# Y-babies_ATtiny84_v04.net
KiCad netlist of a schematic drawn in EAGLE
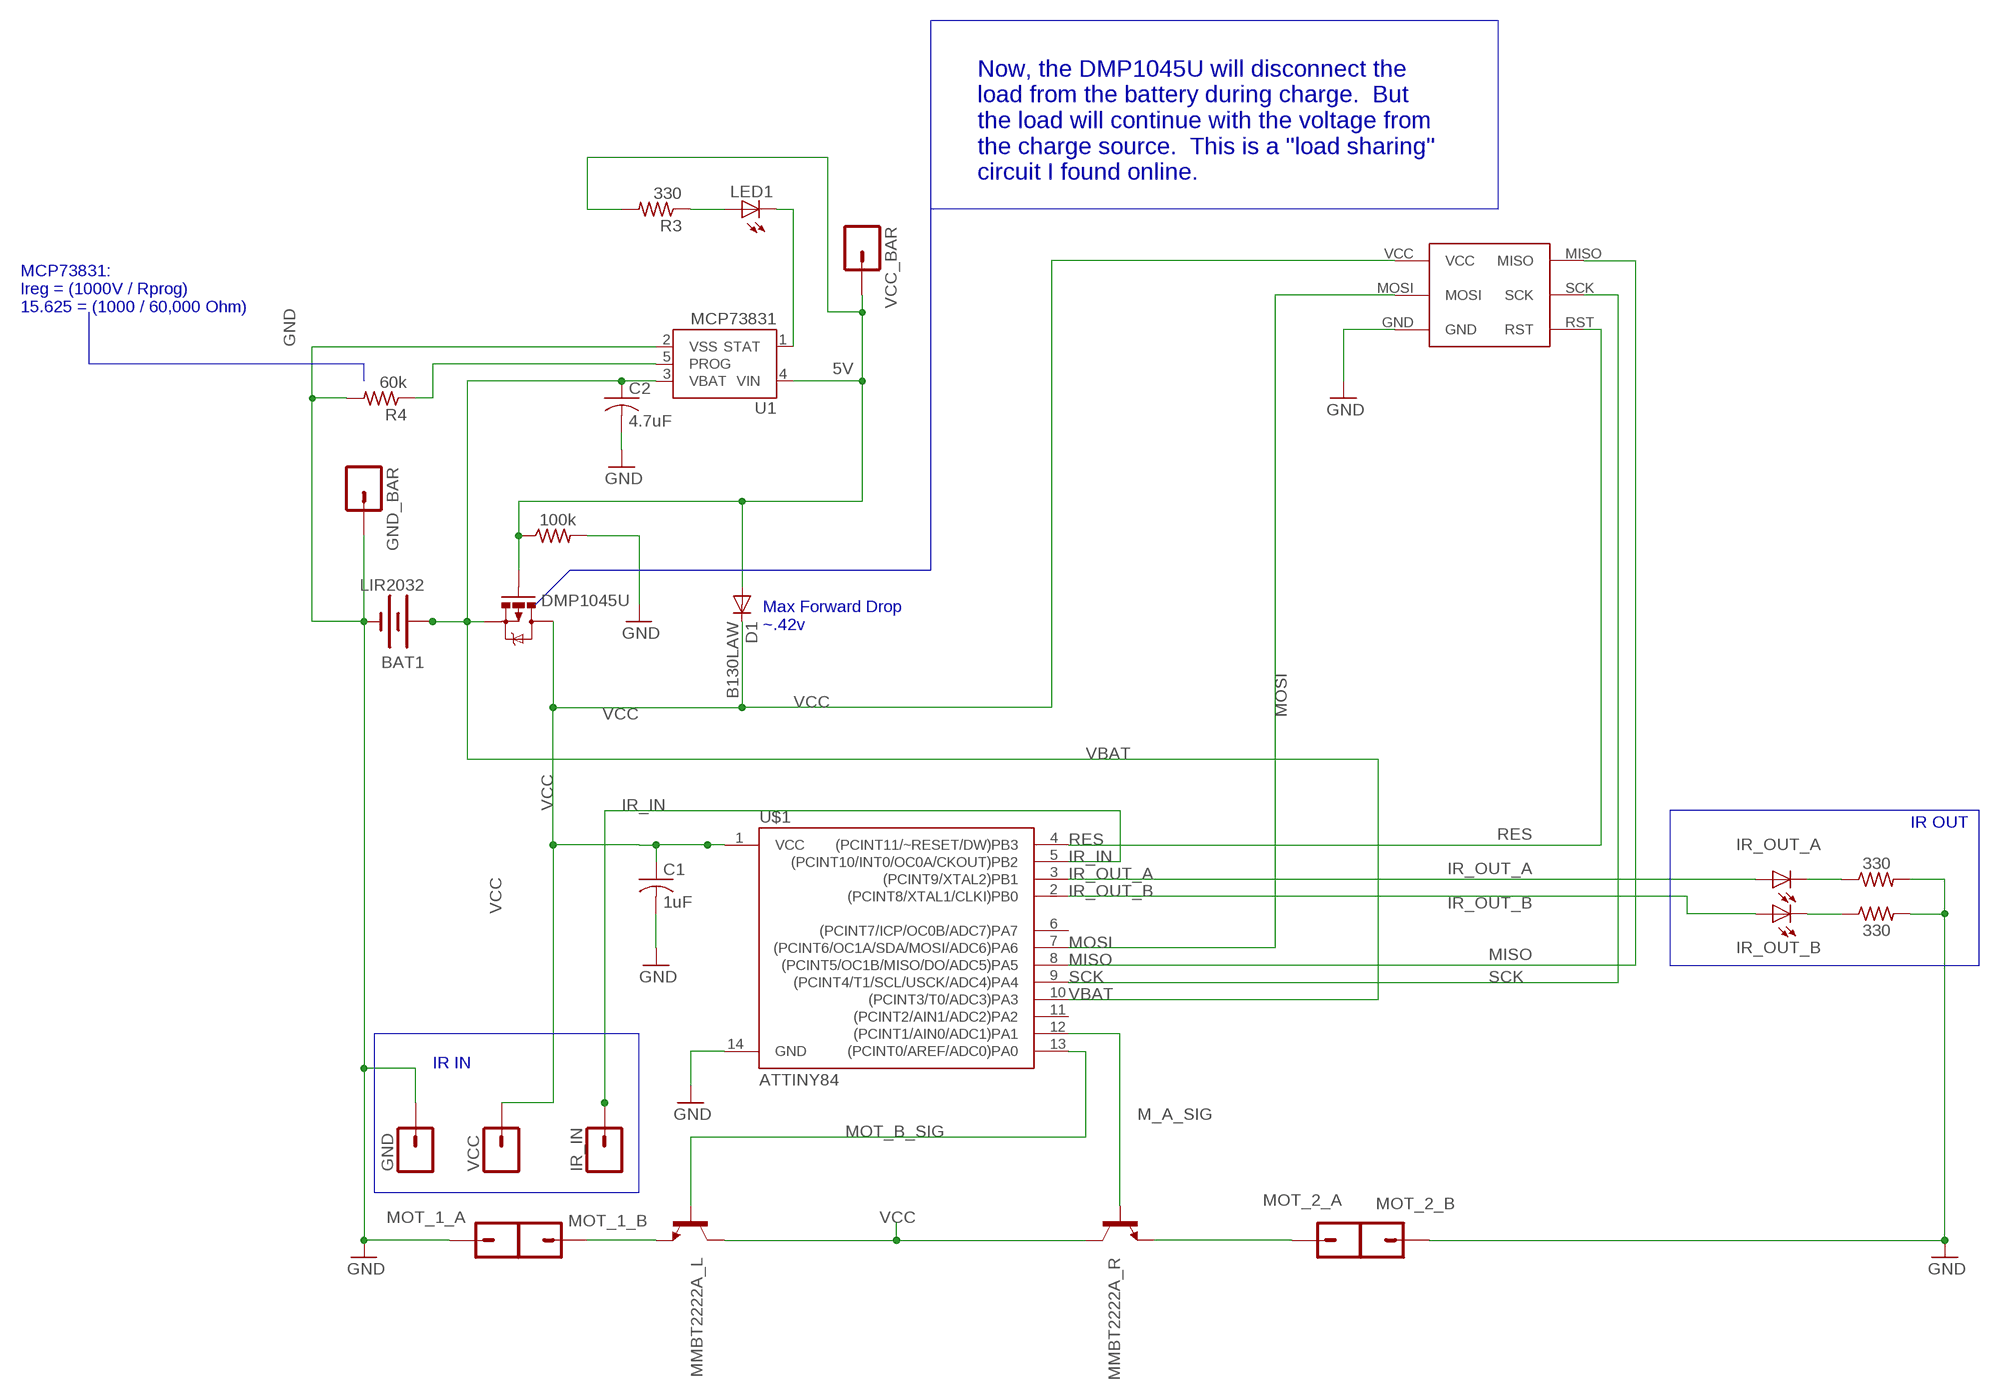
[diagram p0: schematic, sheet 1]

(export (version "E")
  (design (tool "Eeschema 10.0.6"))
  (components
    (comp (ref "BAT1")
      (value "LIR2032")
      (footprint "eagle-import:BATTCOM_20MM_PTH")
      (libsource (lib "eagle-import") (part "BATTERY20PTH"))
    )
    (comp (ref "C1")
      (value "1uF")
      (footprint "eagle-import:C0402K")
      (libsource (lib "eagle-import") (part "C-USC0402K"))
    )
    (comp (ref "C2")
      (value "4.7uF")
      (footprint "eagle-import:C0805K")
      (libsource (lib "eagle-import") (part "C-USC0805K"))
    )
    (comp (ref "D1")
      (value "B130LAW")
      (footprint "eagle-import:SOD123")
      (libsource (lib "eagle-import") (part "DIODE-SOD123"))
    )
    (comp (ref "DMP1045U")
      (value "MOSFET-PCHANNELSMD")
      (footprint "eagle-import:SOT23-3")
      (libsource (lib "eagle-import") (part "MOSFET-PCHANNELSMD"))
    )
    (comp (ref "GND")
      (value "M01PTH")
      (footprint "eagle-import:1X01")
      (libsource (lib "eagle-import") (part "M01PTH"))
    )
    (comp (ref "GND_BAR")
      (value "M01PTH")
      (footprint "eagle-import:1X01")
      (libsource (lib "eagle-import") (part "M01PTH"))
    )
    (comp (ref "IR_IN")
      (value "M01PTH")
      (footprint "eagle-import:1X01")
      (libsource (lib "eagle-import") (part "M01PTH"))
    )
    (comp (ref "IR_OUT_A")
      (value "LED3MM")
      (footprint "eagle-import:LED3MM")
      (libsource (lib "eagle-import") (part "LED3MM"))
    )
    (comp (ref "IR_OUT_B")
      (value "LED3MM")
      (footprint "eagle-import:LED3MM")
      (libsource (lib "eagle-import") (part "LED3MM"))
    )
    (comp (ref "LED1")
      (value "LEDSML0603")
      (footprint "eagle-import:SML0603")
      (libsource (lib "eagle-import") (part "LEDSML0603"))
    )
    (comp (ref "MMBT2222A_L")
      (value "TRANSISTOR_NPNSOT23")
      (footprint "eagle-import:SOT23")
      (libsource (lib "eagle-import") (part "TRANSISTOR_NPNSOT23"))
    )
    (comp (ref "MMBT2222A_R")
      (value "TRANSISTOR_NPNSOT23")
      (footprint "eagle-import:SOT23")
      (libsource (lib "eagle-import") (part "TRANSISTOR_NPNSOT23"))
    )
    (comp (ref "MOT_1_A")
      (value "M01SMD-4.5X1.5")
      (footprint "eagle-import:PAD-1.5X4.5")
      (libsource (lib "eagle-import") (part "M01SMD-4.5X1.5"))
    )
    (comp (ref "MOT_1_B")
      (value "M01SMD-4.5X1.5")
      (footprint "eagle-import:PAD-1.5X4.5")
      (libsource (lib "eagle-import") (part "M01SMD-4.5X1.5"))
    )
    (comp (ref "MOT_2_A")
      (value "M01SMD-4.5X1.5")
      (footprint "eagle-import:PAD-1.5X4.5")
      (libsource (lib "eagle-import") (part "M01SMD-4.5X1.5"))
    )
    (comp (ref "MOT_2_B")
      (value "M01SMD-4.5X1.5")
      (footprint "eagle-import:PAD-1.5X4.5")
      (libsource (lib "eagle-import") (part "M01SMD-4.5X1.5"))
    )
    (comp (ref "R1")
      (value "330")
      (footprint "eagle-import:R0402")
      (libsource (lib "eagle-import") (part "R-US_R0402"))
    )
    (comp (ref "R2")
      (value "330")
      (footprint "eagle-import:R0402")
      (libsource (lib "eagle-import") (part "R-US_R0402"))
    )
    (comp (ref "R3")
      (value "330")
      (footprint "eagle-import:R0402")
      (libsource (lib "eagle-import") (part "R-US_R0402"))
    )
    (comp (ref "R4")
      (value "60k")
      (footprint "eagle-import:R0402")
      (libsource (lib "eagle-import") (part "R-US_R0402"))
    )
    (comp (ref "R5")
      (value "100k")
      (footprint "eagle-import:R0402")
      (libsource (lib "eagle-import") (part "R-US_R0402"))
    )
    (comp (ref "U$1")
      (value "ATTINY84")
      (footprint "eagle-import:SO14")
      (libsource (lib "eagle-import") (part "ATTINY84"))
    )
    (comp (ref "U$2")
      (value "POGO_PIN_SPI_PAD")
      (footprint "eagle-import:POGO_PIN_SPI_PAD")
      (libsource (lib "eagle-import") (part "POGO_PIN_SPI_PAD"))
    )
    (comp (ref "U1")
      (value "MCP73831")
      (footprint "eagle-import:SOT23-5")
      (libsource (lib "eagle-import") (part "MCP73831"))
    )
    (comp (ref "VCC")
      (value "M01PTH")
      (footprint "eagle-import:1X01")
      (libsource (lib "eagle-import") (part "M01PTH"))
    )
    (comp (ref "VCC_BAR")
      (value "M01PTH")
      (footprint "eagle-import:1X01")
      (libsource (lib "eagle-import") (part "M01PTH"))
    )
  )
  (nets
    (net (code "1") (name "/5V") (class "Default")
      (node (ref "D1") (pin "A") (pinfunction "A_A") (pintype "passive"))
      (node (ref "DMP1045U") (pin "1") (pinfunction "G_1") (pintype "passive"))
      (node (ref "R3") (pin "2") (pinfunction "2_2") (pintype "passive"))
      (node (ref "R5") (pin "1") (pinfunction "1_1") (pintype "passive"))
      (node (ref "U1") (pin "4") (pinfunction "VIN_4") (pintype "power_in"))
      (node (ref "VCC_BAR") (pin "1") (pinfunction "1_1") (pintype "passive"))
    )
    (net (code "2") (name "/IR_IN") (class "Default")
      (node (ref "IR_IN") (pin "1") (pinfunction "1_1") (pintype "passive"))
      (node (ref "U$1") (pin "5") (pinfunction "(PCINT10/INT0/OC0A/CKOUT)PB2_5") (pintype "bidirectional"))
    )
    (net (code "3") (name "/IR_OUT_A") (class "Default")
      (node (ref "IR_OUT_A") (pin "A") (pinfunction "A_A") (pintype "passive"))
      (node (ref "U$1") (pin "3") (pinfunction "(PCINT9/XTAL2)PB1_3") (pintype "bidirectional"))
    )
    (net (code "4") (name "/IR_OUT_B") (class "Default")
      (node (ref "IR_OUT_B") (pin "A") (pinfunction "A_A") (pintype "passive"))
      (node (ref "U$1") (pin "2") (pinfunction "(PCINT8/XTAL1/CLKI)PB0_2") (pintype "bidirectional"))
    )
    (net (code "5") (name "/MISO") (class "Default")
      (node (ref "U$1") (pin "8") (pinfunction "(PCINT5/OC1B/MISO/DO/ADC5)PA5_8") (pintype "bidirectional"))
      (node (ref "U$2") (pin "MISO") (pinfunction "MISO_MISO") (pintype "bidirectional"))
    )
    (net (code "6") (name "/MOSI") (class "Default")
      (node (ref "U$1") (pin "7") (pinfunction "(PCINT6/OC1A/SDA/MOSI/ADC6)PA6_7") (pintype "bidirectional"))
      (node (ref "U$2") (pin "MOSI") (pinfunction "MOSI_MOSI") (pintype "bidirectional"))
    )
    (net (code "7") (name "/MOT_B_SIG") (class "Default")
      (node (ref "MMBT2222A_L") (pin "1") (pinfunction "B_1") (pintype "passive"))
      (node (ref "U$1") (pin "13") (pinfunction "(PCINT0/AREF/ADC0)PA0_13") (pintype "bidirectional"))
    )
    (net (code "8") (name "/M_A_SIG") (class "Default")
      (node (ref "MMBT2222A_R") (pin "1") (pinfunction "B_1") (pintype "passive"))
      (node (ref "U$1") (pin "12") (pinfunction "(PCINT1/AIN0/ADC1)PA1_12") (pintype "bidirectional"))
    )
    (net (code "9") (name "/RES") (class "Default")
      (node (ref "U$1") (pin "4") (pinfunction "(PCINT11/~{RESET/DW})PB3_4") (pintype "bidirectional"))
      (node (ref "U$2") (pin "RST") (pinfunction "RST_RST") (pintype "bidirectional"))
    )
    (net (code "10") (name "/SCK") (class "Default")
      (node (ref "U$1") (pin "9") (pinfunction "(PCINT4/T1/SCL/USCK/ADC4)PA4_9") (pintype "bidirectional"))
      (node (ref "U$2") (pin "SCK") (pinfunction "SCK_SCK") (pintype "bidirectional"))
    )
    (net (code "11") (name "/VBAT") (class "Default")
      (node (ref "BAT1") (pin "1") (pinfunction "+_1") (pintype "power_in"))
      (node (ref "C2") (pin "1") (pinfunction "1_1") (pintype "passive"))
      (node (ref "DMP1045U") (pin "2") (pinfunction "S_2") (pintype "passive"))
      (node (ref "U$1") (pin "10") (pinfunction "(PCINT3/T0/ADC3)PA3_10") (pintype "bidirectional"))
      (node (ref "U1") (pin "3") (pinfunction "VBAT_3") (pintype "power_in"))
    )
    (net (code "12") (name "/VCC") (class "Default")
      (node (ref "C1") (pin "1") (pinfunction "1_1") (pintype "passive"))
      (node (ref "D1") (pin "C") (pinfunction "C_C") (pintype "passive"))
      (node (ref "DMP1045U") (pin "3") (pinfunction "D_3") (pintype "passive"))
      (node (ref "MMBT2222A_L") (pin "3") (pinfunction "C_3") (pintype "passive"))
      (node (ref "MMBT2222A_R") (pin "3") (pinfunction "C_3") (pintype "passive"))
      (node (ref "U$1") (pin "1") (pinfunction "VCC_1") (pintype "bidirectional"))
      (node (ref "U$2") (pin "VCC") (pinfunction "VCC_VCC") (pintype "bidirectional"))
      (node (ref "VCC") (pin "1") (pinfunction "1_1") (pintype "passive"))
    )
    (net (code "13") (name "GND") (class "Default")
      (node (ref "BAT1") (pin "2") (pinfunction "-_2") (pintype "power_in"))
      (node (ref "C1") (pin "2") (pinfunction "2_2") (pintype "passive"))
      (node (ref "C2") (pin "2") (pinfunction "2_2") (pintype "passive"))
      (node (ref "GND") (pin "1") (pinfunction "1_1") (pintype "passive"))
      (node (ref "GND_BAR") (pin "1") (pinfunction "1_1") (pintype "passive"))
      (node (ref "MOT_1_A") (pin "P$1") (pinfunction "1_P$1") (pintype "passive"))
      (node (ref "MOT_2_B") (pin "P$1") (pinfunction "1_P$1") (pintype "passive"))
      (node (ref "R1") (pin "2") (pinfunction "2_2") (pintype "passive"))
      (node (ref "R2") (pin "2") (pinfunction "2_2") (pintype "passive"))
      (node (ref "R4") (pin "2") (pinfunction "2_2") (pintype "passive"))
      (node (ref "R5") (pin "2") (pinfunction "2_2") (pintype "passive"))
      (node (ref "U$1") (pin "14") (pinfunction "GND_14") (pintype "bidirectional"))
      (node (ref "U$2") (pin "GND") (pinfunction "GND_GND") (pintype "bidirectional"))
      (node (ref "U1") (pin "2") (pinfunction "VSS_2") (pintype "power_in"))
    )
    (net (code "14") (name "Net-(IR_OUT_A-C)") (class "Default")
      (node (ref "IR_OUT_A") (pin "K") (pinfunction "C_K") (pintype "passive"))
      (node (ref "R1") (pin "1") (pinfunction "1_1") (pintype "passive"))
    )
    (net (code "15") (name "Net-(IR_OUT_B-C)") (class "Default")
      (node (ref "IR_OUT_B") (pin "K") (pinfunction "C_K") (pintype "passive"))
      (node (ref "R2") (pin "1") (pinfunction "1_1") (pintype "passive"))
    )
    (net (code "16") (name "Net-(LED1-PadA)") (class "Default")
      (node (ref "LED1") (pin "A") (pinfunction "A_A") (pintype "passive"))
      (node (ref "R3") (pin "1") (pinfunction "1_1") (pintype "passive"))
    )
    (net (code "17") (name "Net-(MMBT2222A_L-E)") (class "Default")
      (node (ref "MMBT2222A_L") (pin "2") (pinfunction "E_2") (pintype "passive"))
      (node (ref "MOT_1_B") (pin "P$1") (pinfunction "1_P$1") (pintype "passive"))
    )
    (net (code "18") (name "Net-(MMBT2222A_R-E)") (class "Default")
      (node (ref "MMBT2222A_R") (pin "2") (pinfunction "E_2") (pintype "passive"))
      (node (ref "MOT_2_A") (pin "P$1") (pinfunction "1_P$1") (pintype "passive"))
    )
    (net (code "19") (name "Net-(U1-PROG)") (class "Default")
      (node (ref "R4") (pin "1") (pinfunction "1_1") (pintype "passive"))
      (node (ref "U1") (pin "5") (pinfunction "PROG_5") (pintype "input"))
    )
    (net (code "20") (name "Net-(U1-STAT)") (class "Default")
      (node (ref "LED1") (pin "C") (pinfunction "C_C") (pintype "passive"))
      (node (ref "U1") (pin "1") (pinfunction "STAT_1") (pintype "output"))
    )
    (net (code "21") (name "unconnected-(U$1-(PCINT2{slash}AIN1{slash}ADC2)PA2-Pad11)") (class "Default")
      (node (ref "U$1") (pin "11") (pinfunction "(PCINT2/AIN1/ADC2)PA2_11") (pintype "bidirectional"))
    )
    (net (code "22") (name "unconnected-(U$1-(PCINT7{slash}ICP{slash}OC0B{slash}ADC7)PA7-Pad6)") (class "Default")
      (node (ref "U$1") (pin "6") (pinfunction "(PCINT7/ICP/OC0B/ADC7)PA7_6") (pintype "bidirectional"))
    )
  )
)
